# ETHERNET_PHY.net
KiCad netlist of a schematic drawn in Altium Designer
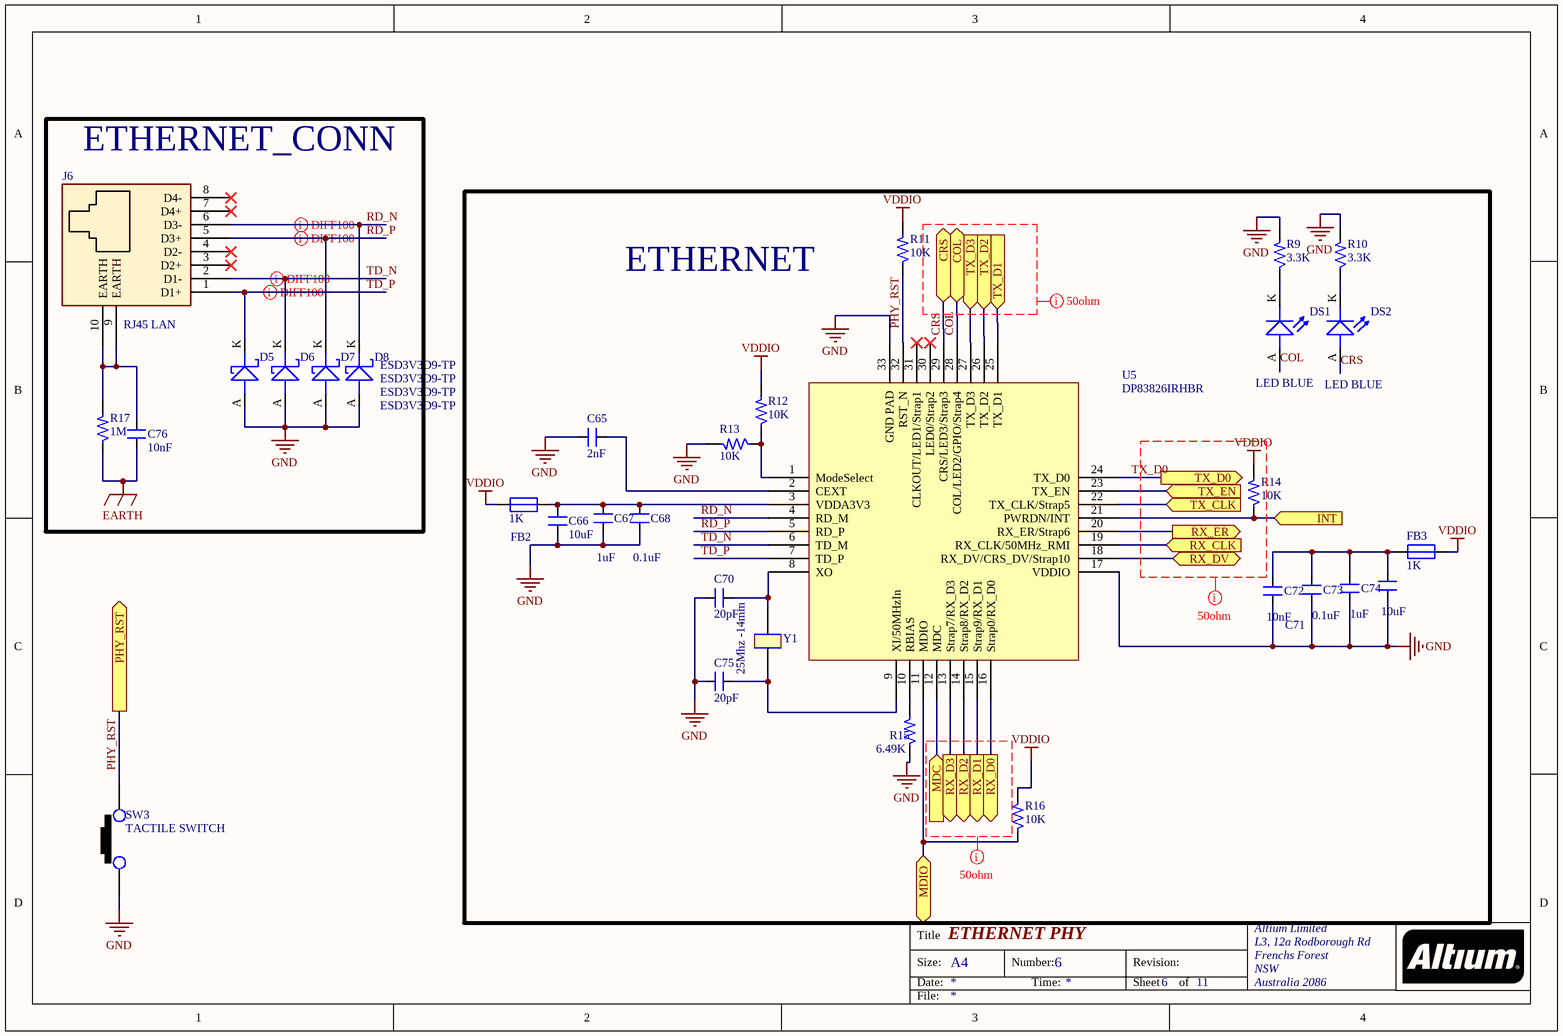
[diagram p0: ETHERNET PHY.SchDoc]

(export (version "E")
  (design (tool "Eeschema 10.0.6"))
  (components
    (comp (ref "C65")
      (value "2nF")
      (footprint "CAP_0805")
      (description "2000pF ±10% 50V Ceramic Capacitor X7R 0805 (2012 Metric)")
      (fields
        (field (name "MANUFACTURER") "Samsung Electro-Mechanics")
        (field (name "MANUFACTURER PART NUMBER") "CL21B202KBANNNC")
      )
      (libsource (lib "ESTEEMPCBLIB") (part "CAP_2nF-50V-10%-0805"))
    )
    (comp (ref "C66")
      (value "10uF")
      (footprint "CAP_1206")
      (description "10µF ±10% 50V Ceramic Capacitor X7R 1206 (3216 Metric)")
      (fields
        (field (name "MANUFACTURER") "KEMET")
        (field (name "MANUFACTURER PART NUMBER") "CL31B106KBHNNNE")
      )
      (libsource (lib "ESTEEMPCBLIB") (part "CAP_10uF-50V-10%-1206"))
    )
    (comp (ref "C67")
      (value "1uF")
      (footprint "CAP_0805")
      (description "1µF ±5% 50V Ceramic Capacitor X7R 0805 (2012 Metric)")
      (fields
        (field (name "MANUFACTURER") "Samsung")
        (field (name "MANUFACTURER PART NUMBER") "CC0805JKX7R9BB105")
      )
      (libsource (lib "ESTEEMPCBLIB") (part "CAP_1uF-50V-5%-0805"))
    )
    (comp (ref "C68")
      (value "0.1uF")
      (footprint "CAP_0805")
      (description "0.1µF ±5% 50V Ceramic Capacitor X7R 0805 (2012 Metric)")
      (fields
        (field (name "MANUFACTURER") "AVX Corporation")
        (field (name "MANUFACTURER PART NUMBER") "08055C104JAT4A")
      )
      (libsource (lib "ESTEEMPCBLIB") (part "CAP_0.1uF-50V-5%-0805"))
    )
    (comp (ref "C70")
      (value "20pF")
      (footprint "CAP_0805")
      (description "±10% 50V Ceramic Capacitor C0G, NP0 0805 (2012 Metric)")
      (fields
        (field (name "MANUFACTURER") "AVX Corporation")
        (field (name "MANUFACTURER PART NUMBER") "08055A200KAT2A")
      )
      (libsource (lib "ESTEEMPCBLIB") (part "CAP_20pF-50V-10%-0805"))
    )
    (comp (ref "C71")
      (value "10uF")
      (footprint "CAP_1206")
      (description "10µF ±10% 50V Ceramic Capacitor X7R 1206 (3216 Metric)")
      (fields
        (field (name "MANUFACTURER") "KEMET")
        (field (name "MANUFACTURER PART NUMBER") "CL31B106KBHNNNE")
      )
      (libsource (lib "ESTEEMPCBLIB") (part "CAP_10uF-50V-10%-1206"))
    )
    (comp (ref "C72")
      (value "10nF")
      (footprint "CAP_P196_102X287_H332_RAD_TH")
      (description "10000pF ±10% 1000V (1kV) Ceramic Capacitor X7R Radial")
      (fields
        (field (name "MANUFACTURER") "Yageo")
        (field (name "MANUFACTURER PART NUMBER") "RDER73A103K2K1H03B")
      )
      (libsource (lib "ESTEEMPCBLIB") (part "CAP_10nF-1KV-10%-RAD-TH"))
    )
    (comp (ref "C73")
      (value "0.1uF")
      (footprint "CAP_0805")
      (description "0.1µF ±5% 50V Ceramic Capacitor X7R 0805 (2012 Metric)")
      (fields
        (field (name "MANUFACTURER") "AVX Corporation")
        (field (name "MANUFACTURER PART NUMBER") "08055C104JAT4A")
      )
      (libsource (lib "ESTEEMPCBLIB") (part "CAP_0.1uF-50V-5%-0805"))
    )
    (comp (ref "C74")
      (value "1uF")
      (footprint "CAP_0805")
      (description "1µF ±5% 50V Ceramic Capacitor X7R 0805 (2012 Metric)")
      (fields
        (field (name "MANUFACTURER") "Samsung")
        (field (name "MANUFACTURER PART NUMBER") "CC0805JKX7R9BB105")
      )
      (libsource (lib "ESTEEMPCBLIB") (part "CAP_1uF-50V-5%-0805"))
    )
    (comp (ref "C75")
      (value "20pF")
      (footprint "CAP_0805")
      (description "±10% 50V Ceramic Capacitor C0G, NP0 0805 (2012 Metric)")
      (fields
        (field (name "MANUFACTURER") "AVX Corporation")
        (field (name "MANUFACTURER PART NUMBER") "08055A200KAT2A")
      )
      (libsource (lib "ESTEEMPCBLIB") (part "CAP_20pF-50V-10%-0805"))
    )
    (comp (ref "C76")
      (value "10nF")
      (footprint "CAP_P196_102X287_H332_RAD_TH")
      (description "10000pF ±10% 1000V (1kV) Ceramic Capacitor X7R Radial")
      (fields
        (field (name "MANUFACTURER") "Yageo")
        (field (name "MANUFACTURER PART NUMBER") "RDER73A103K2K1H03B")
      )
      (libsource (lib "ESTEEMPCBLIB") (part "CAP_10nF-1KV-10%-RAD-TH"))
    )
    (comp (ref "D5")
      (value "ESD3V3D9-TP")
      (footprint "DIO_SOD-923")
      (description "8.8V Clamp 5A (8/20µs) Ipp Tvs Diode Surface Mount SOD-923")
      (fields (field (name "MANUFACTURER") "Micro Commercial Co"))
      (libsource (lib "ESTEEMPCBLIB") (part "DIO-T_3.3V-8.8V-SOD923"))
    )
    (comp (ref "D6")
      (value "ESD3V3D9-TP")
      (footprint "DIO_SOD-923")
      (description "8.8V Clamp 5A (8/20µs) Ipp Tvs Diode Surface Mount SOD-923")
      (fields (field (name "MANUFACTURER") "Micro Commercial Co"))
      (libsource (lib "ESTEEMPCBLIB") (part "DIO-T_3.3V-8.8V-SOD923"))
    )
    (comp (ref "D7")
      (value "ESD3V3D9-TP")
      (footprint "DIO_SOD-923")
      (description "8.8V Clamp 5A (8/20µs) Ipp Tvs Diode Surface Mount SOD-923")
      (fields (field (name "MANUFACTURER") "Micro Commercial Co"))
      (libsource (lib "ESTEEMPCBLIB") (part "DIO-T_3.3V-8.8V-SOD923"))
    )
    (comp (ref "D8")
      (value "ESD3V3D9-TP")
      (footprint "DIO_SOD-923")
      (description "8.8V Clamp 5A (8/20µs) Ipp Tvs Diode Surface Mount SOD-923")
      (fields (field (name "MANUFACTURER") "Micro Commercial Co"))
      (libsource (lib "ESTEEMPCBLIB") (part "DIO-T_3.3V-8.8V-SOD923"))
    )
    (comp (ref "DS1")
      (value "LED BLUE")
      (footprint "LED_0805")
      (description "Blue 470nm LED Indication - Discrete 3.3V 0805 (2012 Metric)")
      (fields
        (field (name "MANUFACTURER") "Vishay Lite-On")
        (field (name "MANUFACTURER PART NUMBER") "LTST-C171TBKT")
      )
      (libsource (lib "ESTEEMPCBLIB") (part "LED_BLUE-3V3-20mA-0805"))
    )
    (comp (ref "DS2")
      (value "LED BLUE")
      (footprint "LED_0805")
      (description "Blue 470nm LED Indication - Discrete 3.3V 0805 (2012 Metric)")
      (fields
        (field (name "MANUFACTURER") "Vishay Lite-On")
        (field (name "MANUFACTURER PART NUMBER") "LTST-C171TBKT")
      )
      (libsource (lib "ESTEEMPCBLIB") (part "LED_BLUE-3V3-20mA-0805"))
    )
    (comp (ref "FB2")
      (value "1K")
      (footprint "IND_0805")
      (description "1 kOhms @ 100MHz 1 Power Line Ferrite Bead 0805 (2012 Metric) 1.6A")
      (fields
        (field (name "MANUFACTURER") "Laird")
        (field (name "MANUFACTURER PART NUMBER") "BLM21SP102SH1D")
      )
      (libsource (lib "ESTEEMPCBLIB") (part "FB_1K-100MHZ-1.6A-0805"))
    )
    (comp (ref "FB3")
      (value "1K")
      (footprint "IND_0805")
      (description "1 kOhms @ 100MHz 1 Power Line Ferrite Bead 0805 (2012 Metric) 1.6A")
      (fields
        (field (name "MANUFACTURER") "Laird")
        (field (name "MANUFACTURER PART NUMBER") "BLM21SP102SH1D")
      )
      (libsource (lib "ESTEEMPCBLIB") (part "FB_1K-100MHZ-1.6A-0805"))
    )
    (comp (ref "J6")
      (value "RJ45 LAN")
      (footprint "CON10_P106_RJ45_TH_ST")
      (description "8 Pins, 2 Row 2.54mm Pitch, right angle Connector, male")
      (fields
        (field (name "MANUFACTURER") "Assmann")
        (field (name "MANUFACTURER PART NUMBER") "A-2004-2-4-LPS-N-R")
      )
      (libsource (lib "ESTEEMPCBLIB") (part "CON-SKT-RJ_8C8P-RA-TH"))
    )
    (comp (ref "R9")
      (value "3.3K")
      (footprint "RES_0805")
      (description "3.3 kOhms ±1% 0.125W, 1/8W Chip Resistor 0805 (2012 Metric) Thick Film")
      (fields (field (name "MANUFACTURER") "Panasonic") (field (name "MANUFACTURER PART NUMBER") "1623214-1"))
      (libsource (lib "ESTEEMPCBLIB") (part "RES_3.3K-0.125W-1%-0805"))
    )
    (comp (ref "R10")
      (value "3.3K")
      (footprint "RES_0805")
      (description "3.3 kOhms ±1% 0.125W, 1/8W Chip Resistor 0805 (2012 Metric) Thick Film")
      (fields (field (name "MANUFACTURER") "Panasonic") (field (name "MANUFACTURER PART NUMBER") "1623214-1"))
      (libsource (lib "ESTEEMPCBLIB") (part "RES_3.3K-0.125W-1%-0805"))
    )
    (comp (ref "R11")
      (value "10K")
      (footprint "RES_0805")
      (description "10 kOhms ±1% 0.125W, 1/8W Chip Resistor 0805 (2012 Metric) Automotive AEC-Q200 Thick Film")
      (fields (field (name "MANUFACTURER") "CTS") (field (name "MANUFACTURER PART NUMBER") "WR08X1002FTL"))
      (libsource (lib "ESTEEMPCBLIB") (part "RES_10K-0.125W-1%-0805"))
    )
    (comp (ref "R12")
      (value "10K")
      (footprint "RES_0805")
      (description "10 kOhms ±1% 0.125W, 1/8W Chip Resistor 0805 (2012 Metric) Automotive AEC-Q200 Thick Film")
      (fields (field (name "MANUFACTURER") "CTS") (field (name "MANUFACTURER PART NUMBER") "WR08X1002FTL"))
      (libsource (lib "ESTEEMPCBLIB") (part "RES_10K-0.125W-1%-0805"))
    )
    (comp (ref "R13")
      (value "10K")
      (footprint "RES_0805")
      (description "10 kOhms ±1% 0.125W, 1/8W Chip Resistor 0805 (2012 Metric) Automotive AEC-Q200 Thick Film")
      (fields (field (name "MANUFACTURER") "CTS") (field (name "MANUFACTURER PART NUMBER") "WR08X1002FTL"))
      (libsource (lib "ESTEEMPCBLIB") (part "RES_10K-0.125W-1%-0805"))
    )
    (comp (ref "R14")
      (value "10K")
      (footprint "RES_0805")
      (description "10 kOhms ±1% 0.125W, 1/8W Chip Resistor 0805 (2012 Metric) Automotive AEC-Q200 Thick Film")
      (fields (field (name "MANUFACTURER") "CTS") (field (name "MANUFACTURER PART NUMBER") "WR08X1002FTL"))
      (libsource (lib "ESTEEMPCBLIB") (part "RES_10K-0.125W-1%-0805"))
    )
    (comp (ref "R15")
      (value "6.49K")
      (footprint "RES_0805")
      (description "6.49 kOhms ±1% 0.125W, 1/8W Chip Resistor 0805 (2012 Metric) Moisture Resistant Thick Film")
      (fields
        (field (name "MANUFACTURER") "Stackpole Electronics")
        (field (name "MANUFACTURER PART NUMBER") "RC0805FR-076K49L")
      )
      (libsource (lib "ESTEEMPCBLIB") (part "RES_6.49K-0.125W-1%-0805"))
    )
    (comp (ref "R16")
      (value "10K")
      (footprint "RES_0805")
      (description "10 kOhms ±1% 0.125W, 1/8W Chip Resistor 0805 (2012 Metric) Automotive AEC-Q200 Thick Film")
      (fields (field (name "MANUFACTURER") "CTS") (field (name "MANUFACTURER PART NUMBER") "WR08X1002FTL"))
      (libsource (lib "ESTEEMPCBLIB") (part "RES_10K-0.125W-1%-0805"))
    )
    (comp (ref "R17")
      (value "1M")
      (footprint "RES_0805")
      (description "1 MOhms ±1% 0.125W, 1/8W Chip Resistor 0805 (2012 Metric) Automotive AEC-Q200 Thick Film")
      (fields (field (name "MANUFACTURER") "Walsin") (field (name "MANUFACTURER PART NUMBER") "WR08X1004FTL"))
      (libsource (lib "ESTEEMPCBLIB") (part "RES_1M-0.125W-1%-0805"))
    )
    (comp (ref "SW3")
      (value "TACTILE SWITCH")
      (footprint "SW_342_SMD")
      (description "Tactile Switch SPST-NO Top Actuated Surface Mount")
      (fields
        (field (name "MANUFACTURER") "ITT C&K")
        (field (name "MANUFACTURER PART NUMBER") "RS-282G05A3-SMRT")
      )
      (libsource (lib "ESTEEMPCBLIB") (part "SW1_RS-282G05A3-SMRT-SMD"))
    )
    (comp (ref "U5")
      (value "DP83826IRHBR")
      (footprint "VQFN32_19_218_23X9_SMD")
      (fields (field (name "MANUFACTURER") "Texas Instruments"))
      (libsource (lib "ESTEEMPCBLIB") (part "IC_DP83826IRHBR"))
    )
    (comp (ref "Y1")
      (value "25Mhz -14mm")
      (footprint "XTAL_314_240X47_SMD")
      (description "25MHz ±30ppm Crystal 20pF 30 Ohms HC-49/US")
      (fields
        (field (name "MANUFACTURER") "Abracon")
        (field (name "MANUFACTURER PART NUMBER") "FOXSDLF/250F-20")
      )
      (libsource (lib "ESTEEMPCBLIB") (part "XTAL_25Mhz-FOXSDLF/250F-20"))
    )
  )
  (nets
    (net (code "1") (name "/COL") (class "Default")
      (node (ref "DS1") (pin "A") (pinfunction "ANODE_A") (pintype "passive"))
      (node (ref "U5") (pin "28") (pinfunction "COL/LED2/GPIO/Strap4_28") (pintype "passive"))
    )
    (net (code "2") (name "/CRS") (class "Default")
      (node (ref "DS2") (pin "A") (pinfunction "ANODE_A") (pintype "passive"))
      (node (ref "U5") (pin "29") (pinfunction "CRS/LED3/Strap3_29") (pintype "passive"))
    )
    (net (code "3") (name "/INT") (class "Default")
      (node (ref "R14") (pin "1") (pinfunction "1_1") (pintype "passive"))
      (node (ref "U5") (pin "21") (pinfunction "PWRDN/INT_21") (pintype "passive"))
    )
    (net (code "4") (name "/MDC") (class "Default")
      (node (ref "U5") (pin "12") (pinfunction "MDC_12") (pintype "passive"))
    )
    (net (code "5") (name "/MDIO") (class "Default")
      (node (ref "R16") (pin "1") (pinfunction "1_1") (pintype "passive"))
      (node (ref "U5") (pin "11") (pinfunction "MDIO_11") (pintype "passive"))
    )
    (net (code "6") (name "/PHY_RST") (class "Default")
      (node (ref "R11") (pin "1") (pinfunction "1_1") (pintype "passive"))
      (node (ref "SW3") (pin "2") (pinfunction "2_2") (pintype "passive"))
      (node (ref "U5") (pin "32") (pinfunction "RST_N_32") (pintype "passive"))
    )
    (net (code "7") (name "/RD_N") (class "Default")
      (node (ref "D8") (pin "K") (pinfunction "K_K") (pintype "passive"))
      (node (ref "J6") (pin "6") (pinfunction "D3-_6") (pintype "passive"))
      (node (ref "U5") (pin "4") (pinfunction "RD_M_4") (pintype "passive"))
    )
    (net (code "8") (name "/RD_P") (class "Default")
      (node (ref "D7") (pin "K") (pinfunction "K_K") (pintype "passive"))
      (node (ref "J6") (pin "5") (pinfunction "D3+_5") (pintype "passive"))
      (node (ref "U5") (pin "5") (pinfunction "RD_P_5") (pintype "passive"))
    )
    (net (code "9") (name "/RX_CLK") (class "Default")
      (node (ref "U5") (pin "19") (pinfunction "RX_CLK/50MHz_RMI_19") (pintype "passive"))
    )
    (net (code "10") (name "/RX_D0") (class "Default")
      (node (ref "U5") (pin "16") (pinfunction "Strap0/RX_D0_16") (pintype "passive"))
    )
    (net (code "11") (name "/RX_D1") (class "Default")
      (node (ref "U5") (pin "15") (pinfunction "Strap9/RX_D1_15") (pintype "passive"))
    )
    (net (code "12") (name "/RX_D2") (class "Default")
      (node (ref "U5") (pin "14") (pinfunction "Strap8/RX_D2_14") (pintype "passive"))
    )
    (net (code "13") (name "/RX_D3") (class "Default")
      (node (ref "U5") (pin "13") (pinfunction "Strap7/RX_D3_13") (pintype "passive"))
    )
    (net (code "14") (name "/RX_DV") (class "Default")
      (node (ref "U5") (pin "18") (pinfunction "RX_DV/CRS_DV/Strap10_18") (pintype "passive"))
    )
    (net (code "15") (name "/RX_ER") (class "Default")
      (node (ref "U5") (pin "20") (pinfunction "RX_ER/Strap6_20") (pintype "passive"))
    )
    (net (code "16") (name "/TD_N") (class "Default")
      (node (ref "D6") (pin "K") (pinfunction "K_K") (pintype "passive"))
      (node (ref "J6") (pin "2") (pinfunction "D1-_2") (pintype "passive"))
      (node (ref "U5") (pin "6") (pinfunction "TD_M_6") (pintype "passive"))
    )
    (net (code "17") (name "/TD_P") (class "Default")
      (node (ref "D5") (pin "K") (pinfunction "K_K") (pintype "passive"))
      (node (ref "J6") (pin "1") (pinfunction "D1+_1") (pintype "passive"))
      (node (ref "U5") (pin "7") (pinfunction "TD_P_7") (pintype "passive"))
    )
    (net (code "18") (name "/TX_CLK") (class "Default")
      (node (ref "U5") (pin "22") (pinfunction "TX_CLK/Strap5_22") (pintype "passive"))
    )
    (net (code "19") (name "/TX_D0") (class "Default")
      (node (ref "U5") (pin "24") (pinfunction "TX_D0_24") (pintype "passive"))
    )
    (net (code "20") (name "/TX_D1") (class "Default")
      (node (ref "U5") (pin "25") (pinfunction "TX_D1_25") (pintype "passive"))
    )
    (net (code "21") (name "/TX_D2") (class "Default")
      (node (ref "U5") (pin "26") (pinfunction "TX_D2_26") (pintype "passive"))
    )
    (net (code "22") (name "/TX_D3") (class "Default")
      (node (ref "U5") (pin "27") (pinfunction "TX_D3_27") (pintype "passive"))
    )
    (net (code "23") (name "/TX_EN") (class "Default")
      (node (ref "U5") (pin "23") (pinfunction "TX_EN_23") (pintype "passive"))
    )
    (net (code "24") (name "EARTH") (class "Default")
      (node (ref "C76") (pin "1") (pinfunction "1_1") (pintype "passive"))
      (node (ref "R17") (pin "1") (pinfunction "1_1") (pintype "passive"))
    )
    (net (code "25") (name "GND") (class "Default")
      (node (ref "C65") (pin "2") (pinfunction "2_2") (pintype "passive"))
      (node (ref "C66") (pin "1") (pinfunction "1_1") (pintype "passive"))
      (node (ref "C67") (pin "1") (pinfunction "1_1") (pintype "passive"))
      (node (ref "C68") (pin "1") (pinfunction "1_1") (pintype "passive"))
      (node (ref "C70") (pin "2") (pinfunction "2_2") (pintype "passive"))
      (node (ref "C71") (pin "2") (pinfunction "2_2") (pintype "passive"))
      (node (ref "C72") (pin "2") (pinfunction "2_2") (pintype "passive"))
      (node (ref "C73") (pin "2") (pinfunction "2_2") (pintype "passive"))
      (node (ref "C74") (pin "2") (pinfunction "2_2") (pintype "passive"))
      (node (ref "C75") (pin "2") (pinfunction "2_2") (pintype "passive"))
      (node (ref "D5") (pin "A") (pinfunction "A_A") (pintype "passive"))
      (node (ref "D6") (pin "A") (pinfunction "A_A") (pintype "passive"))
      (node (ref "D7") (pin "A") (pinfunction "A_A") (pintype "passive"))
      (node (ref "D8") (pin "A") (pinfunction "A_A") (pintype "passive"))
      (node (ref "R10") (pin "2") (pinfunction "2_2") (pintype "passive"))
      (node (ref "R13") (pin "2") (pinfunction "2_2") (pintype "passive"))
      (node (ref "R15") (pin "1") (pinfunction "1_1") (pintype "passive"))
      (node (ref "R9") (pin "2") (pinfunction "2_2") (pintype "passive"))
      (node (ref "SW3") (pin "1") (pinfunction "1_1") (pintype "passive"))
      (node (ref "U5") (pin "17") (pinfunction "VDDIO_17") (pintype "passive"))
      (node (ref "U5") (pin "33") (pinfunction "GND_PAD_33") (pintype "passive"))
    )
    (net (code "26") (name "Net-(C71-Pad1)") (class "Default")
      (node (ref "C71") (pin "1") (pinfunction "1_1") (pintype "passive"))
      (node (ref "C72") (pin "1") (pinfunction "1_1") (pintype "passive"))
      (node (ref "C73") (pin "1") (pinfunction "1_1") (pintype "passive"))
      (node (ref "C74") (pin "1") (pinfunction "1_1") (pintype "passive"))
      (node (ref "FB3") (pin "1") (pinfunction "1_1") (pintype "passive"))
    )
    (net (code "27") (name "Net-(C76-Pad2)") (class "Default")
      (node (ref "C76") (pin "2") (pinfunction "2_2") (pintype "passive"))
      (node (ref "J6") (pin "10") (pinfunction "EARTH_10") (pintype "passive"))
      (node (ref "J6") (pin "9") (pinfunction "EARTH_9") (pintype "passive"))
      (node (ref "R17") (pin "2") (pinfunction "2_2") (pintype "passive"))
    )
    (net (code "28") (name "Net-(DS1-CATHODE)") (class "Default")
      (node (ref "DS1") (pin "K") (pinfunction "CATHODE_K") (pintype "passive"))
      (node (ref "R9") (pin "1") (pinfunction "1_1") (pintype "passive"))
    )
    (net (code "29") (name "Net-(DS2-CATHODE)") (class "Default")
      (node (ref "DS2") (pin "K") (pinfunction "CATHODE_K") (pintype "passive"))
      (node (ref "R10") (pin "1") (pinfunction "1_1") (pintype "passive"))
    )
    (net (code "30") (name "Net-(U5-CEXT)") (class "Default")
      (node (ref "C65") (pin "1") (pinfunction "1_1") (pintype "passive"))
      (node (ref "U5") (pin "2") (pinfunction "CEXT_2") (pintype "passive"))
    )
    (net (code "31") (name "Net-(U5-ModeSelect)") (class "Default")
      (node (ref "R12") (pin "1") (pinfunction "1_1") (pintype "passive"))
      (node (ref "R13") (pin "1") (pinfunction "1_1") (pintype "passive"))
      (node (ref "U5") (pin "1") (pinfunction "ModeSelect_1") (pintype "passive"))
    )
    (net (code "32") (name "Net-(U5-RBIAS)") (class "Default")
      (node (ref "R15") (pin "2") (pinfunction "2_2") (pintype "passive"))
      (node (ref "U5") (pin "10") (pinfunction "RBIAS_10") (pintype "passive"))
    )
    (net (code "33") (name "Net-(U5-VDDA3V3)") (class "Default")
      (node (ref "C66") (pin "2") (pinfunction "2_2") (pintype "passive"))
      (node (ref "C67") (pin "2") (pinfunction "2_2") (pintype "passive"))
      (node (ref "C68") (pin "2") (pinfunction "2_2") (pintype "passive"))
      (node (ref "FB2") (pin "2") (pinfunction "2_2") (pintype "passive"))
      (node (ref "U5") (pin "3") (pinfunction "VDDA3V3_3") (pintype "passive"))
    )
    (net (code "34") (name "Net-(U5-XI{slash}50MHzIn)") (class "Default")
      (node (ref "C75") (pin "1") (pinfunction "1_1") (pintype "passive"))
      (node (ref "U5") (pin "9") (pinfunction "XI/50MHzIn_9") (pintype "passive"))
      (node (ref "Y1") (pin "1") (pinfunction "1_1") (pintype "passive"))
    )
    (net (code "35") (name "Net-(U5-XO)") (class "Default")
      (node (ref "C70") (pin "1") (pinfunction "1_1") (pintype "passive"))
      (node (ref "U5") (pin "8") (pinfunction "XO_8") (pintype "passive"))
      (node (ref "Y1") (pin "2") (pinfunction "2_2") (pintype "passive"))
    )
    (net (code "36") (name "VDDIO") (class "Default")
      (node (ref "FB2") (pin "1") (pinfunction "1_1") (pintype "passive"))
      (node (ref "FB3") (pin "2") (pinfunction "2_2") (pintype "passive"))
      (node (ref "R11") (pin "2") (pinfunction "2_2") (pintype "passive"))
      (node (ref "R12") (pin "2") (pinfunction "2_2") (pintype "passive"))
      (node (ref "R14") (pin "2") (pinfunction "2_2") (pintype "passive"))
      (node (ref "R16") (pin "2") (pinfunction "2_2") (pintype "passive"))
    )
    (net (code "37") (name "unconnected-(J6-D2+-Pad3)") (class "Default")
      (node (ref "J6") (pin "3") (pinfunction "D2+_3") (pintype "passive+no_connect"))
    )
    (net (code "38") (name "unconnected-(J6-D2--Pad4)") (class "Default")
      (node (ref "J6") (pin "4") (pinfunction "D2-_4") (pintype "passive+no_connect"))
    )
    (net (code "39") (name "unconnected-(J6-D4+-Pad7)") (class "Default")
      (node (ref "J6") (pin "7") (pinfunction "D4+_7") (pintype "passive+no_connect"))
    )
    (net (code "40") (name "unconnected-(J6-D4--Pad8)") (class "Default")
      (node (ref "J6") (pin "8") (pinfunction "D4-_8") (pintype "passive+no_connect"))
    )
    (net (code "41") (name "unconnected-(U5-CLKOUT{slash}LED1{slash}Strap1-Pad31)") (class "Default")
      (node (ref "U5") (pin "31") (pinfunction "CLKOUT/LED1/Strap1_31") (pintype "passive+no_connect"))
    )
    (net (code "42") (name "unconnected-(U5-LED0{slash}Strap2-Pad30)") (class "Default")
      (node (ref "U5") (pin "30") (pinfunction "LED0/Strap2_30") (pintype "passive+no_connect"))
    )
  )
)
